# ChristmasTree.net
KiCad netlist of a schematic drawn in EAGLE
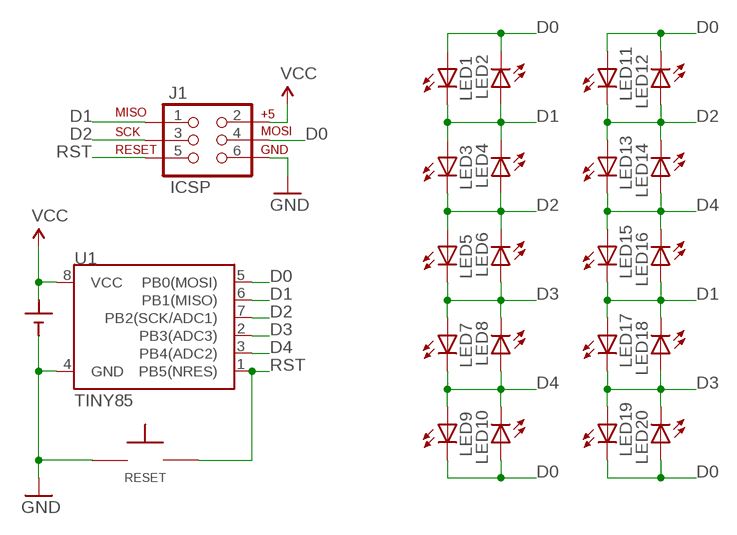
[diagram p0: schematic, sheet 1]

(export (version "E")
  (design (tool "Eeschema 10.0.6"))
  (components
    (comp (ref "BATT")
      (value "CR2032")
      (footprint "eagle-import:CR2032-THRU")
      (libsource (lib "eagle-import") (part "BATTCR2032_THRU"))
    )
    (comp (ref "J1")
      (value "ICSP")
      (footprint "eagle-import:2X3-NS")
      (libsource (lib "eagle-import") (part "AVR_SPI_PRG_6LABELED"))
    )
    (comp (ref "LED1")
      (value "LED5MM")
      (footprint "eagle-import:LED5MM")
      (libsource (lib "eagle-import") (part "LED5MM"))
    )
    (comp (ref "LED2")
      (value "LED5MM")
      (footprint "eagle-import:LED5MM")
      (libsource (lib "eagle-import") (part "LED5MM"))
    )
    (comp (ref "LED3")
      (value "LED5MM")
      (footprint "eagle-import:LED5MM")
      (libsource (lib "eagle-import") (part "LED5MM"))
    )
    (comp (ref "LED4")
      (value "LED5MM")
      (footprint "eagle-import:LED5MM")
      (libsource (lib "eagle-import") (part "LED5MM"))
    )
    (comp (ref "LED5")
      (value "LED5MM")
      (footprint "eagle-import:LED5MM")
      (libsource (lib "eagle-import") (part "LED5MM"))
    )
    (comp (ref "LED6")
      (value "LED5MM")
      (footprint "eagle-import:LED5MM")
      (libsource (lib "eagle-import") (part "LED5MM"))
    )
    (comp (ref "LED7")
      (value "LED5MM")
      (footprint "eagle-import:LED5MM")
      (libsource (lib "eagle-import") (part "LED5MM"))
    )
    (comp (ref "LED8")
      (value "LED5MM")
      (footprint "eagle-import:LED5MM")
      (libsource (lib "eagle-import") (part "LED5MM"))
    )
    (comp (ref "LED9")
      (value "LED5MM")
      (footprint "eagle-import:LED5MM")
      (libsource (lib "eagle-import") (part "LED5MM"))
    )
    (comp (ref "LED10")
      (value "LED5MM")
      (footprint "eagle-import:LED5MM")
      (libsource (lib "eagle-import") (part "LED5MM"))
    )
    (comp (ref "LED11")
      (value "LED5MM")
      (footprint "eagle-import:LED5MM")
      (libsource (lib "eagle-import") (part "LED5MM"))
    )
    (comp (ref "LED12")
      (value "LED5MM")
      (footprint "eagle-import:LED5MM")
      (libsource (lib "eagle-import") (part "LED5MM"))
    )
    (comp (ref "LED13")
      (value "LED5MM")
      (footprint "eagle-import:LED5MM")
      (libsource (lib "eagle-import") (part "LED5MM"))
    )
    (comp (ref "LED14")
      (value "LED5MM")
      (footprint "eagle-import:LED5MM")
      (libsource (lib "eagle-import") (part "LED5MM"))
    )
    (comp (ref "LED15")
      (value "LED5MM")
      (footprint "eagle-import:LED5MM")
      (libsource (lib "eagle-import") (part "LED5MM"))
    )
    (comp (ref "LED16")
      (value "LED5MM")
      (footprint "eagle-import:LED5MM")
      (libsource (lib "eagle-import") (part "LED5MM"))
    )
    (comp (ref "LED17")
      (value "LED5MM")
      (footprint "eagle-import:LED5MM")
      (libsource (lib "eagle-import") (part "LED5MM"))
    )
    (comp (ref "LED18")
      (value "LED5MM")
      (footprint "eagle-import:LED5MM")
      (libsource (lib "eagle-import") (part "LED5MM"))
    )
    (comp (ref "LED19")
      (value "LED5MM")
      (footprint "eagle-import:LED5MM")
      (libsource (lib "eagle-import") (part "LED5MM"))
    )
    (comp (ref "LED20")
      (value "LED5MM")
      (footprint "eagle-import:LED5MM")
      (libsource (lib "eagle-import") (part "LED5MM"))
    )
    (comp (ref "RESET")
      (value "TAC_SPST_NO")
      (footprint "eagle-import:TAC_SPST_NO")
      (libsource (lib "eagle-import") (part "TAC_SPST_NO"))
    )
    (comp (ref "U1")
      (value "TINY85")
      (footprint "eagle-import:DIP08")
      (libsource (lib "eagle-import") (part "ATTINY45TINY85-20-DIP"))
    )
  )
  (nets
    (net (code "1") (name "/D0") (class "Default")
      (node (ref "J1") (pin "4") (pinfunction "MOSI_4") (pintype "passive"))
      (node (ref "LED1") (pin "A") (pinfunction "A_A") (pintype "passive"))
      (node (ref "LED10") (pin "A") (pinfunction "A_A") (pintype "passive"))
      (node (ref "LED11") (pin "A") (pinfunction "A_A") (pintype "passive"))
      (node (ref "LED12") (pin "K") (pinfunction "C_K") (pintype "passive"))
      (node (ref "LED19") (pin "K") (pinfunction "C_K") (pintype "passive"))
      (node (ref "LED2") (pin "K") (pinfunction "C_K") (pintype "passive"))
      (node (ref "LED20") (pin "A") (pinfunction "A_A") (pintype "passive"))
      (node (ref "LED9") (pin "K") (pinfunction "C_K") (pintype "passive"))
      (node (ref "U1") (pin "5") (pinfunction "PB0(MOSI)_5") (pintype "bidirectional"))
    )
    (net (code "2") (name "/D1") (class "Default")
      (node (ref "J1") (pin "1") (pinfunction "MISO_1") (pintype "passive"))
      (node (ref "LED1") (pin "K") (pinfunction "C_K") (pintype "passive"))
      (node (ref "LED15") (pin "K") (pinfunction "C_K") (pintype "passive"))
      (node (ref "LED16") (pin "A") (pinfunction "A_A") (pintype "passive"))
      (node (ref "LED17") (pin "A") (pinfunction "A_A") (pintype "passive"))
      (node (ref "LED18") (pin "K") (pinfunction "C_K") (pintype "passive"))
      (node (ref "LED2") (pin "A") (pinfunction "A_A") (pintype "passive"))
      (node (ref "LED3") (pin "A") (pinfunction "A_A") (pintype "passive"))
      (node (ref "LED4") (pin "K") (pinfunction "C_K") (pintype "passive"))
      (node (ref "U1") (pin "6") (pinfunction "PB1(MISO)_6") (pintype "bidirectional"))
    )
    (net (code "3") (name "/D2") (class "Default")
      (node (ref "J1") (pin "3") (pinfunction "SCK_3") (pintype "passive"))
      (node (ref "LED11") (pin "K") (pinfunction "C_K") (pintype "passive"))
      (node (ref "LED12") (pin "A") (pinfunction "A_A") (pintype "passive"))
      (node (ref "LED13") (pin "A") (pinfunction "A_A") (pintype "passive"))
      (node (ref "LED14") (pin "K") (pinfunction "C_K") (pintype "passive"))
      (node (ref "LED3") (pin "K") (pinfunction "C_K") (pintype "passive"))
      (node (ref "LED4") (pin "A") (pinfunction "A_A") (pintype "passive"))
      (node (ref "LED5") (pin "A") (pinfunction "A_A") (pintype "passive"))
      (node (ref "LED6") (pin "K") (pinfunction "C_K") (pintype "passive"))
      (node (ref "U1") (pin "7") (pinfunction "PB2(SCK/ADC1)_7") (pintype "bidirectional"))
    )
    (net (code "4") (name "/D3") (class "Default")
      (node (ref "LED17") (pin "K") (pinfunction "C_K") (pintype "passive"))
      (node (ref "LED18") (pin "A") (pinfunction "A_A") (pintype "passive"))
      (node (ref "LED19") (pin "A") (pinfunction "A_A") (pintype "passive"))
      (node (ref "LED20") (pin "K") (pinfunction "C_K") (pintype "passive"))
      (node (ref "LED5") (pin "K") (pinfunction "C_K") (pintype "passive"))
      (node (ref "LED6") (pin "A") (pinfunction "A_A") (pintype "passive"))
      (node (ref "LED7") (pin "A") (pinfunction "A_A") (pintype "passive"))
      (node (ref "LED8") (pin "K") (pinfunction "C_K") (pintype "passive"))
      (node (ref "U1") (pin "2") (pinfunction "PB3(ADC3)_2") (pintype "bidirectional"))
    )
    (net (code "5") (name "/D4") (class "Default")
      (node (ref "LED10") (pin "K") (pinfunction "C_K") (pintype "passive"))
      (node (ref "LED13") (pin "K") (pinfunction "C_K") (pintype "passive"))
      (node (ref "LED14") (pin "A") (pinfunction "A_A") (pintype "passive"))
      (node (ref "LED15") (pin "A") (pinfunction "A_A") (pintype "passive"))
      (node (ref "LED16") (pin "K") (pinfunction "C_K") (pintype "passive"))
      (node (ref "LED7") (pin "K") (pinfunction "C_K") (pintype "passive"))
      (node (ref "LED8") (pin "A") (pinfunction "A_A") (pintype "passive"))
      (node (ref "LED9") (pin "A") (pinfunction "A_A") (pintype "passive"))
      (node (ref "U1") (pin "3") (pinfunction "PB4(ADC2)_3") (pintype "bidirectional"))
    )
    (net (code "6") (name "/RST") (class "Default")
      (node (ref "J1") (pin "5") (pinfunction "RST_5") (pintype "passive"))
      (node (ref "RESET") (pin "P$2") (pinfunction "P$2_P$2") (pintype "bidirectional"))
      (node (ref "U1") (pin "1") (pinfunction "PB5(NRES)_1") (pintype "bidirectional"))
    )
    (net (code "7") (name "GND") (class "Default")
      (node (ref "BATT") (pin "-") (pinfunction "-_-") (pintype "power_in"))
      (node (ref "J1") (pin "6") (pinfunction "GND_6") (pintype "passive"))
      (node (ref "RESET") (pin "P$1") (pinfunction "P$1_P$1") (pintype "bidirectional"))
      (node (ref "U1") (pin "4") (pinfunction "GND_4") (pintype "bidirectional"))
    )
    (net (code "8") (name "VCC") (class "Default")
      (node (ref "BATT") (pin "+1") (pinfunction "+_+1") (pintype "power_in"))
      (node (ref "J1") (pin "2") (pinfunction "V+_2") (pintype "passive"))
      (node (ref "U1") (pin "8") (pinfunction "VCC_8") (pintype "bidirectional"))
    )
  )
)
